# Moteino.net
KiCad netlist of a schematic drawn in EAGLE
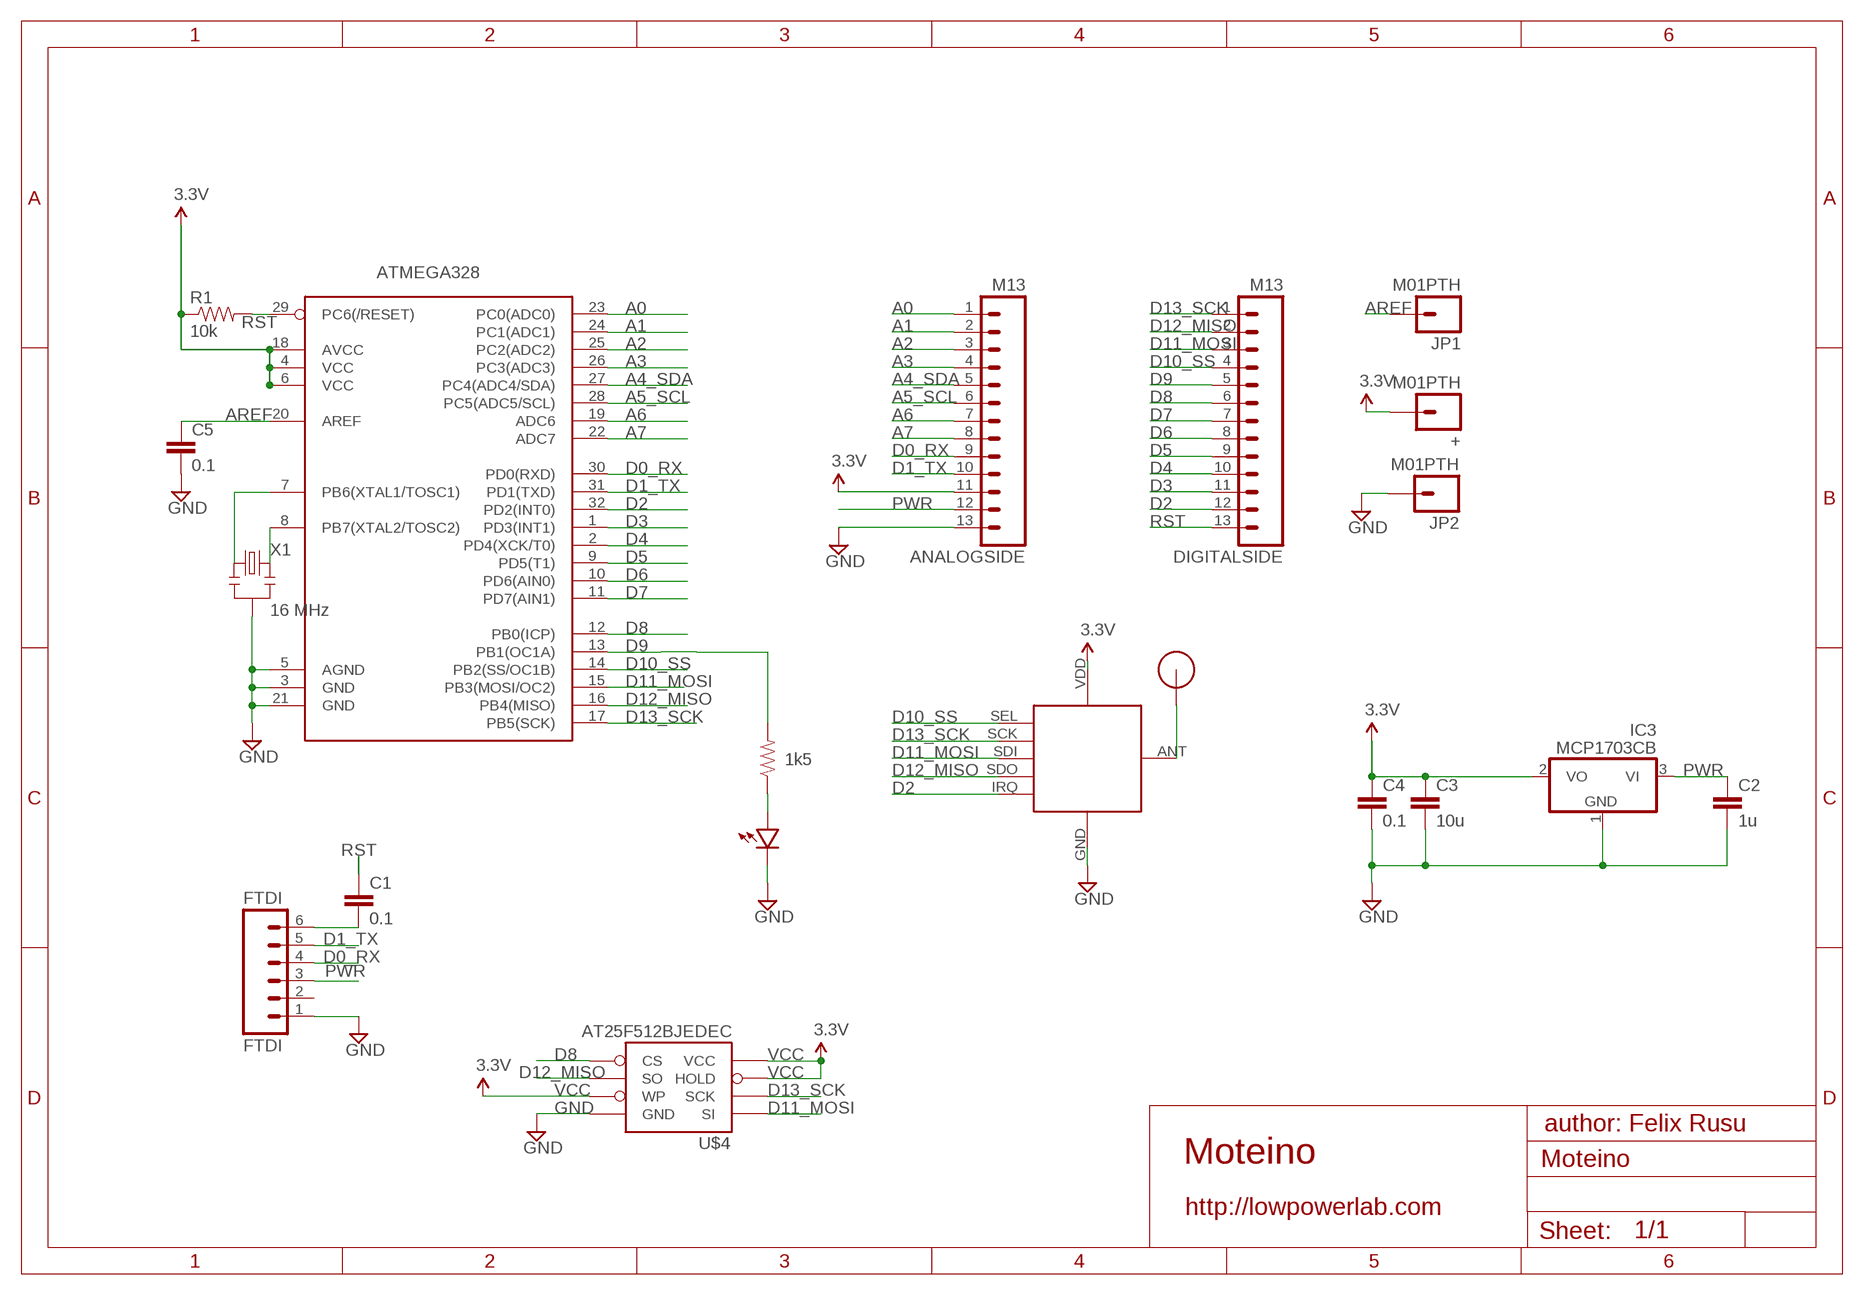
[diagram p0: schematic, sheet 1]

(export (version "E")
  (design (tool "Eeschema 10.0.6"))
  (components
    (comp (ref "+")
      (value "M01PTH")
      (footprint "eagle-import:1X01")
      (libsource (lib "eagle-import") (part "M01PTH"))
    )
    (comp (ref "ANALOGSIDE")
      (value "M13")
      (footprint "eagle-import:1X13")
      (libsource (lib "eagle-import") (part "M13"))
    )
    (comp (ref "ATMEGA328")
      (value "ATMega-328")
      (footprint "eagle-import:TQFP32-08")
      (libsource (lib "eagle-import") (part "ATMEGA168/328TQFP32"))
    )
    (comp (ref "C1")
      (value "0.1")
      (footprint "eagle-import:0603-CAP")
      (libsource (lib "eagle-import") (part "CAP0603-CAP"))
    )
    (comp (ref "C2")
      (value "1u")
      (footprint "eagle-import:0603-CAP")
      (libsource (lib "eagle-import") (part "CAP0603-CAP"))
    )
    (comp (ref "C3")
      (value "10u")
      (footprint "eagle-import:0805-CAP")
      (libsource (lib "eagle-import") (part "CAP0805-CAP"))
    )
    (comp (ref "C4")
      (value "0.1")
      (footprint "eagle-import:0603-CAP")
      (libsource (lib "eagle-import") (part "CAP0603-CAP"))
    )
    (comp (ref "C5")
      (value "0.1")
      (footprint "eagle-import:0603-CAP")
      (libsource (lib "eagle-import") (part "CAP0603-CAP"))
    )
    (comp (ref "DIGITALSIDE")
      (value "M13")
      (footprint "eagle-import:1X13")
      (libsource (lib "eagle-import") (part "M13"))
    )
    (comp (ref "FTDI")
      (value "FTDI")
      (footprint "eagle-import:1X06")
      (libsource (lib "eagle-import") (part "M06SIP"))
    )
    (comp (ref "IC3")
      (value "MCP1703CB")
      (footprint "eagle-import:SOT23")
      (libsource (lib "eagle-import") (part "MCP1703CB"))
    )
    (comp (ref "JP1")
      (value "M01PTH")
      (footprint "eagle-import:1X01")
      (libsource (lib "eagle-import") (part "M01PTH"))
    )
    (comp (ref "JP2")
      (value "M01PTH")
      (footprint "eagle-import:1X01")
      (libsource (lib "eagle-import") (part "M01PTH"))
    )
    (comp (ref "R1")
      (value "10k")
      (footprint "eagle-import:0603-RES")
      (libsource (lib "eagle-import") (part "RESISTOR0603-RES"))
    )
    (comp (ref "R2")
      (value "1k5")
      (footprint "eagle-import:0603-RES")
      (libsource (lib "eagle-import") (part "RESISTOR0603-RES"))
    )
    (comp (ref "RFM12B")
      (value "RFM12B_MINPADS")
      (footprint "eagle-import:RFM12B-MINPADS")
      (libsource (lib "eagle-import") (part "RFM12B_MINPADS"))
    )
    (comp (ref "U$1")
      (value "RFM12B_ANTENNA")
      (footprint "eagle-import:RFM12B-ANTENNA")
      (libsource (lib "eagle-import") (part "RFM12B_ANTENNA"))
    )
    (comp (ref "U$2")
      (value "LED0603")
      (footprint "eagle-import:0603-LED")
      (libsource (lib "eagle-import") (part "LED0603"))
    )
    (comp (ref "U$4")
      (value "AT25F512BJEDEC")
      (footprint "eagle-import:SO08")
      (libsource (lib "eagle-import") (part "AT25F512BJEDEC"))
    )
    (comp (ref "X1")
      (value "16 MHz")
      (footprint "eagle-import:RESONATOR-SMD")
      (libsource (lib "eagle-import") (part "RESONATORSMD"))
    )
  )
  (nets
    (net (code "1") (name "/A0") (class "Default")
      (node (ref "ANALOGSIDE") (pin "1") (pinfunction "1_1") (pintype "passive"))
      (node (ref "ATMEGA328") (pin "23") (pinfunction "PC0(ADC0)_23") (pintype "bidirectional"))
    )
    (net (code "2") (name "/A1") (class "Default")
      (node (ref "ANALOGSIDE") (pin "2") (pinfunction "2_2") (pintype "passive"))
      (node (ref "ATMEGA328") (pin "24") (pinfunction "PC1(ADC1)_24") (pintype "bidirectional"))
    )
    (net (code "3") (name "/A2") (class "Default")
      (node (ref "ANALOGSIDE") (pin "3") (pinfunction "3_3") (pintype "passive"))
      (node (ref "ATMEGA328") (pin "25") (pinfunction "PC2(ADC2)_25") (pintype "bidirectional"))
    )
    (net (code "4") (name "/A3") (class "Default")
      (node (ref "ANALOGSIDE") (pin "4") (pinfunction "4_4") (pintype "passive"))
      (node (ref "ATMEGA328") (pin "26") (pinfunction "PC3(ADC3)_26") (pintype "bidirectional"))
    )
    (net (code "5") (name "/A4_SDA") (class "Default")
      (node (ref "ANALOGSIDE") (pin "5") (pinfunction "5_5") (pintype "passive"))
      (node (ref "ATMEGA328") (pin "27") (pinfunction "PC4(ADC4/SDA)_27") (pintype "bidirectional"))
    )
    (net (code "6") (name "/A5_SCL") (class "Default")
      (node (ref "ANALOGSIDE") (pin "6") (pinfunction "6_6") (pintype "passive"))
      (node (ref "ATMEGA328") (pin "28") (pinfunction "PC5(ADC5/SCL)_28") (pintype "bidirectional"))
    )
    (net (code "7") (name "/A6") (class "Default")
      (node (ref "ANALOGSIDE") (pin "7") (pinfunction "7_7") (pintype "passive"))
      (node (ref "ATMEGA328") (pin "19") (pinfunction "ADC6_19") (pintype "bidirectional"))
    )
    (net (code "8") (name "/A7") (class "Default")
      (node (ref "ANALOGSIDE") (pin "8") (pinfunction "8_8") (pintype "passive"))
      (node (ref "ATMEGA328") (pin "22") (pinfunction "ADC7_22") (pintype "bidirectional"))
    )
    (net (code "9") (name "/AREF") (class "Default")
      (node (ref "ATMEGA328") (pin "20") (pinfunction "AREF_20") (pintype "bidirectional"))
      (node (ref "C5") (pin "1") (pinfunction "1_1") (pintype "passive"))
      (node (ref "JP1") (pin "1") (pinfunction "1_1") (pintype "passive"))
    )
    (net (code "10") (name "/D0_RX") (class "Default")
      (node (ref "ANALOGSIDE") (pin "9") (pinfunction "9_9") (pintype "passive"))
      (node (ref "ATMEGA328") (pin "30") (pinfunction "PD0(RXD)_30") (pintype "bidirectional"))
      (node (ref "FTDI") (pin "4") (pinfunction "4_4") (pintype "passive"))
    )
    (net (code "11") (name "/D1_TX") (class "Default")
      (node (ref "ANALOGSIDE") (pin "10") (pinfunction "10_10") (pintype "passive"))
      (node (ref "ATMEGA328") (pin "31") (pinfunction "PD1(TXD)_31") (pintype "bidirectional"))
      (node (ref "FTDI") (pin "5") (pinfunction "5_5") (pintype "passive"))
    )
    (net (code "12") (name "/D2") (class "Default")
      (node (ref "ATMEGA328") (pin "32") (pinfunction "PD2(INT0)_32") (pintype "bidirectional"))
      (node (ref "DIGITALSIDE") (pin "12") (pinfunction "12_12") (pintype "passive"))
      (node (ref "RFM12B") (pin "IRQ") (pinfunction "IRQ_IRQ") (pintype "bidirectional"))
    )
    (net (code "13") (name "/D3") (class "Default")
      (node (ref "ATMEGA328") (pin "1") (pinfunction "PD3(INT1)_1") (pintype "bidirectional"))
      (node (ref "DIGITALSIDE") (pin "11") (pinfunction "11_11") (pintype "passive"))
    )
    (net (code "14") (name "/D4") (class "Default")
      (node (ref "ATMEGA328") (pin "2") (pinfunction "PD4(XCK/T0)_2") (pintype "bidirectional"))
      (node (ref "DIGITALSIDE") (pin "10") (pinfunction "10_10") (pintype "passive"))
    )
    (net (code "15") (name "/D5") (class "Default")
      (node (ref "ATMEGA328") (pin "9") (pinfunction "PD5(T1)_9") (pintype "bidirectional"))
      (node (ref "DIGITALSIDE") (pin "9") (pinfunction "9_9") (pintype "passive"))
    )
    (net (code "16") (name "/D6") (class "Default")
      (node (ref "ATMEGA328") (pin "10") (pinfunction "PD6(AIN0)_10") (pintype "bidirectional"))
      (node (ref "DIGITALSIDE") (pin "8") (pinfunction "8_8") (pintype "passive"))
    )
    (net (code "17") (name "/D7") (class "Default")
      (node (ref "ATMEGA328") (pin "11") (pinfunction "PD7(AIN1)_11") (pintype "bidirectional"))
      (node (ref "DIGITALSIDE") (pin "7") (pinfunction "7_7") (pintype "passive"))
    )
    (net (code "18") (name "/D8") (class "Default")
      (node (ref "ATMEGA328") (pin "12") (pinfunction "PB0(ICP)_12") (pintype "bidirectional"))
      (node (ref "DIGITALSIDE") (pin "6") (pinfunction "6_6") (pintype "passive"))
      (node (ref "U$4") (pin "1_CS") (pinfunction "CS_1_CS") (pintype "bidirectional"))
    )
    (net (code "19") (name "/D9") (class "Default")
      (node (ref "ATMEGA328") (pin "13") (pinfunction "PB1(OC1A)_13") (pintype "bidirectional"))
      (node (ref "DIGITALSIDE") (pin "5") (pinfunction "5_5") (pintype "passive"))
      (node (ref "R2") (pin "2") (pinfunction "2_2") (pintype "passive"))
    )
    (net (code "20") (name "/D10_SS") (class "Default")
      (node (ref "ATMEGA328") (pin "14") (pinfunction "PB2(SS/OC1B)_14") (pintype "bidirectional"))
      (node (ref "DIGITALSIDE") (pin "4") (pinfunction "4_4") (pintype "passive"))
      (node (ref "RFM12B") (pin "SEL") (pinfunction "SEL_SEL") (pintype "bidirectional"))
    )
    (net (code "21") (name "/D11_MOSI") (class "Default")
      (node (ref "ATMEGA328") (pin "15") (pinfunction "PB3(MOSI/OC2)_15") (pintype "bidirectional"))
      (node (ref "DIGITALSIDE") (pin "3") (pinfunction "3_3") (pintype "passive"))
      (node (ref "RFM12B") (pin "SDI") (pinfunction "SDI/MOSI_SDI") (pintype "bidirectional"))
      (node (ref "U$4") (pin "5_SI") (pinfunction "SI_5_SI") (pintype "bidirectional"))
    )
    (net (code "22") (name "/D12_MISO") (class "Default")
      (node (ref "ATMEGA328") (pin "16") (pinfunction "PB4(MISO)_16") (pintype "bidirectional"))
      (node (ref "DIGITALSIDE") (pin "2") (pinfunction "2_2") (pintype "passive"))
      (node (ref "RFM12B") (pin "SDO") (pinfunction "SDO/MISO_SDO") (pintype "bidirectional"))
      (node (ref "U$4") (pin "2_SO") (pinfunction "SO_2_SO") (pintype "bidirectional"))
    )
    (net (code "23") (name "/D13_SCK") (class "Default")
      (node (ref "ATMEGA328") (pin "17") (pinfunction "PB5(SCK)_17") (pintype "bidirectional"))
      (node (ref "DIGITALSIDE") (pin "1") (pinfunction "1_1") (pintype "passive"))
      (node (ref "RFM12B") (pin "SCK") (pinfunction "SCK_SCK") (pintype "bidirectional"))
      (node (ref "U$4") (pin "6_SCK") (pinfunction "SCK_6_SCK") (pintype "bidirectional"))
    )
    (net (code "24") (name "/PWR") (class "Default")
      (node (ref "ANALOGSIDE") (pin "12") (pinfunction "12_12") (pintype "passive"))
      (node (ref "C2") (pin "1") (pinfunction "1_1") (pintype "passive"))
      (node (ref "FTDI") (pin "3") (pinfunction "3_3") (pintype "passive"))
      (node (ref "IC3") (pin "3") (pinfunction "VI_3") (pintype "input"))
    )
    (net (code "25") (name "/RST") (class "Default")
      (node (ref "ATMEGA328") (pin "29") (pinfunction "PC6(/RESET)_29") (pintype "bidirectional"))
      (node (ref "C1") (pin "1") (pinfunction "1_1") (pintype "passive"))
      (node (ref "DIGITALSIDE") (pin "13") (pinfunction "13_13") (pintype "passive"))
      (node (ref "R1") (pin "2") (pinfunction "2_2") (pintype "passive"))
    )
    (net (code "26") (name "3.3V") (class "Default")
      (node (ref "+") (pin "1") (pinfunction "1_1") (pintype "passive"))
      (node (ref "ANALOGSIDE") (pin "11") (pinfunction "11_11") (pintype "passive"))
      (node (ref "ATMEGA328") (pin "18") (pinfunction "AVCC_18") (pintype "bidirectional"))
      (node (ref "ATMEGA328") (pin "4") (pinfunction "VCC_4") (pintype "bidirectional"))
      (node (ref "ATMEGA328") (pin "6") (pinfunction "VCC_6") (pintype "bidirectional"))
      (node (ref "C3") (pin "1") (pinfunction "1_1") (pintype "passive"))
      (node (ref "C4") (pin "1") (pinfunction "1_1") (pintype "passive"))
      (node (ref "IC3") (pin "2") (pinfunction "VO_2") (pintype "passive"))
      (node (ref "R1") (pin "1") (pinfunction "1_1") (pintype "passive"))
      (node (ref "RFM12B") (pin "VDD") (pinfunction "VDD_VDD") (pintype "bidirectional"))
      (node (ref "U$4") (pin "3_WP") (pinfunction "WP_3_WP") (pintype "bidirectional"))
      (node (ref "U$4") (pin "7_HOLD") (pinfunction "HOLD_7_HOLD") (pintype "bidirectional"))
      (node (ref "U$4") (pin "8_VCC") (pinfunction "VCC_8_VCC") (pintype "bidirectional"))
    )
    (net (code "27") (name "GND") (class "Default")
      (node (ref "ANALOGSIDE") (pin "13") (pinfunction "13_13") (pintype "passive"))
      (node (ref "ATMEGA328") (pin "21") (pinfunction "GND_21") (pintype "bidirectional"))
      (node (ref "ATMEGA328") (pin "3") (pinfunction "GND_3") (pintype "bidirectional"))
      (node (ref "ATMEGA328") (pin "5") (pinfunction "AGND_5") (pintype "bidirectional"))
      (node (ref "C2") (pin "2") (pinfunction "2_2") (pintype "passive"))
      (node (ref "C3") (pin "2") (pinfunction "2_2") (pintype "passive"))
      (node (ref "C4") (pin "2") (pinfunction "2_2") (pintype "passive"))
      (node (ref "C5") (pin "2") (pinfunction "2_2") (pintype "passive"))
      (node (ref "FTDI") (pin "1") (pinfunction "1_1") (pintype "passive"))
      (node (ref "IC3") (pin "1") (pinfunction "GND_1") (pintype "passive"))
      (node (ref "JP2") (pin "1") (pinfunction "1_1") (pintype "passive"))
      (node (ref "RFM12B") (pin "GND") (pinfunction "GND_GND") (pintype "bidirectional"))
      (node (ref "U$2") (pin "MINUS") (pinfunction "MINUS_MINUS") (pintype "passive"))
      (node (ref "U$4") (pin "4_GND") (pinfunction "GND_4_GND") (pintype "bidirectional"))
      (node (ref "X1") (pin "2") (pinfunction "2_2") (pintype "passive"))
    )
    (net (code "28") (name "Net-(ATMEGA328-PB6(XTAL1{slash}TOSC1))") (class "Default")
      (node (ref "ATMEGA328") (pin "7") (pinfunction "PB6(XTAL1/TOSC1)_7") (pintype "bidirectional"))
      (node (ref "X1") (pin "1") (pinfunction "1_1") (pintype "passive"))
    )
    (net (code "29") (name "Net-(ATMEGA328-PB7(XTAL2{slash}TOSC2))") (class "Default")
      (node (ref "ATMEGA328") (pin "8") (pinfunction "PB7(XTAL2/TOSC2)_8") (pintype "bidirectional"))
      (node (ref "X1") (pin "3") (pinfunction "3_3") (pintype "passive"))
    )
    (net (code "30") (name "Net-(C1-Pad2)") (class "Default")
      (node (ref "C1") (pin "2") (pinfunction "2_2") (pintype "passive"))
      (node (ref "FTDI") (pin "6") (pinfunction "6_6") (pintype "passive"))
    )
    (net (code "31") (name "Net-(R2-Pad1)") (class "Default")
      (node (ref "R2") (pin "1") (pinfunction "1_1") (pintype "passive"))
      (node (ref "U$2") (pin "PLUS") (pinfunction "PLUS_PLUS") (pintype "passive"))
    )
    (net (code "32") (name "Net-(U$1-1)") (class "Default")
      (node (ref "RFM12B") (pin "ANT") (pinfunction "ANT_ANT") (pintype "bidirectional"))
      (node (ref "U$1") (pin "P$1") (pinfunction "1_P$1") (pintype "bidirectional"))
    )
    (net (code "33") (name "unconnected-(FTDI-Pad2)") (class "Default")
      (node (ref "FTDI") (pin "2") (pinfunction "2_2") (pintype "passive"))
    )
  )
)
